# PushButtonDummy.net
KiCad netlist of a schematic drawn in EAGLE
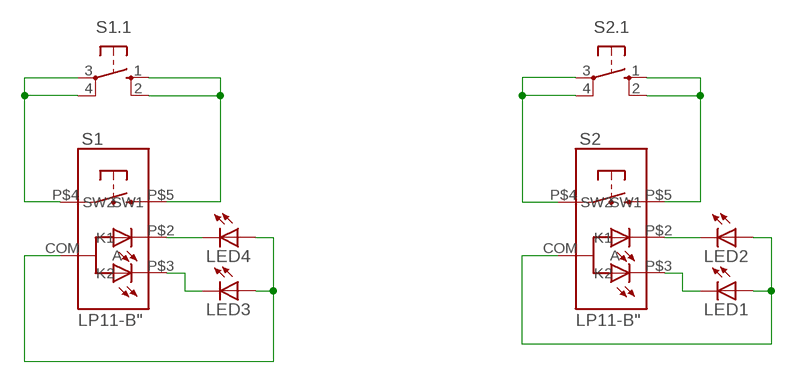
[diagram p0: schematic, sheet 1]

(export (version "E")
  (design (tool "Eeschema 10.0.6"))
  (components
    (comp (ref "LED1")
      (value "LED3MM")
      (footprint "eagle-import:LED3MM")
      (libsource (lib "eagle-import") (part "LED3MM"))
    )
    (comp (ref "LED2")
      (value "LED3MM")
      (footprint "eagle-import:LED3MM")
      (libsource (lib "eagle-import") (part "LED3MM"))
    )
    (comp (ref "LED3")
      (value "LED3MM")
      (footprint "eagle-import:LED3MM")
      (libsource (lib "eagle-import") (part "LED3MM"))
    )
    (comp (ref "LED4")
      (value "LED3MM")
      (footprint "eagle-import:LED3MM")
      (libsource (lib "eagle-import") (part "LED3MM"))
    )
    (comp (ref "S1")
      (value "LP11-B\"")
      (footprint "eagle-import:LP11")
      (libsource (lib "eagle-import") (part "LP11-B{dblquote}"))
    )
    (comp (ref "S1.1")
      (value "10-XX")
      (footprint "eagle-import:B3F-10XX")
      (fields (field (name "MPN") "B3F-1000"))
      (libsource (lib "eagle-import") (part "10-XX"))
    )
    (comp (ref "S2")
      (value "LP11-B\"")
      (footprint "eagle-import:LP11")
      (libsource (lib "eagle-import") (part "LP11-B{dblquote}"))
    )
    (comp (ref "S2.1")
      (value "10-XX")
      (footprint "eagle-import:B3F-10XX")
      (fields (field (name "MPN") "B3F-1000"))
      (libsource (lib "eagle-import") (part "10-XX"))
    )
  )
  (nets
    (net (code "1") (name "Net-(LED1-C)") (class "Default")
      (node (ref "LED1") (pin "K") (pinfunction "C_K") (pintype "passive"))
      (node (ref "S2") (pin "P$3") (pinfunction "K2_P$3") (pintype "bidirectional"))
    )
    (net (code "2") (name "Net-(LED2-C)") (class "Default")
      (node (ref "LED2") (pin "K") (pinfunction "C_K") (pintype "passive"))
      (node (ref "S2") (pin "P$2") (pinfunction "K1_P$2") (pintype "bidirectional"))
    )
    (net (code "3") (name "Net-(LED3-C)") (class "Default")
      (node (ref "LED3") (pin "K") (pinfunction "C_K") (pintype "passive"))
      (node (ref "S1") (pin "P$3") (pinfunction "K2_P$3") (pintype "bidirectional"))
    )
    (net (code "4") (name "Net-(LED4-C)") (class "Default")
      (node (ref "LED4") (pin "K") (pinfunction "C_K") (pintype "passive"))
      (node (ref "S1") (pin "P$2") (pinfunction "K1_P$2") (pintype "bidirectional"))
    )
    (net (code "5") (name "Net-(S1-A)") (class "Default")
      (node (ref "LED3") (pin "A") (pinfunction "A_A") (pintype "passive"))
      (node (ref "LED4") (pin "A") (pinfunction "A_A") (pintype "passive"))
      (node (ref "S1") (pin "COM") (pinfunction "A_COM") (pintype "bidirectional"))
    )
    (net (code "6") (name "Net-(S1-SW1)") (class "Default")
      (node (ref "S1") (pin "P$4") (pinfunction "SW1_P$4") (pintype "bidirectional"))
      (node (ref "S1.1") (pin "3") (pinfunction "P_3") (pintype "passive"))
      (node (ref "S1.1") (pin "4") (pinfunction "P1_4") (pintype "passive"))
    )
    (net (code "7") (name "Net-(S1-SW2)") (class "Default")
      (node (ref "S1") (pin "P$5") (pinfunction "SW2_P$5") (pintype "bidirectional"))
      (node (ref "S1.1") (pin "1") (pinfunction "S_1") (pintype "passive"))
      (node (ref "S1.1") (pin "2") (pinfunction "S1_2") (pintype "passive"))
    )
    (net (code "8") (name "Net-(S2-A)") (class "Default")
      (node (ref "LED1") (pin "A") (pinfunction "A_A") (pintype "passive"))
      (node (ref "LED2") (pin "A") (pinfunction "A_A") (pintype "passive"))
      (node (ref "S2") (pin "COM") (pinfunction "A_COM") (pintype "bidirectional"))
    )
    (net (code "9") (name "Net-(S2-SW1)") (class "Default")
      (node (ref "S2") (pin "P$4") (pinfunction "SW1_P$4") (pintype "bidirectional"))
      (node (ref "S2.1") (pin "3") (pinfunction "P_3") (pintype "passive"))
      (node (ref "S2.1") (pin "4") (pinfunction "P1_4") (pintype "passive"))
    )
    (net (code "10") (name "Net-(S2-SW2)") (class "Default")
      (node (ref "S2") (pin "P$5") (pinfunction "SW2_P$5") (pintype "bidirectional"))
      (node (ref "S2.1") (pin "1") (pinfunction "S_1") (pintype "passive"))
      (node (ref "S2.1") (pin "2") (pinfunction "S1_2") (pintype "passive"))
    )
  )
)
